# aux_power_systems.net
KiCad netlist of a schematic drawn in EAGLE
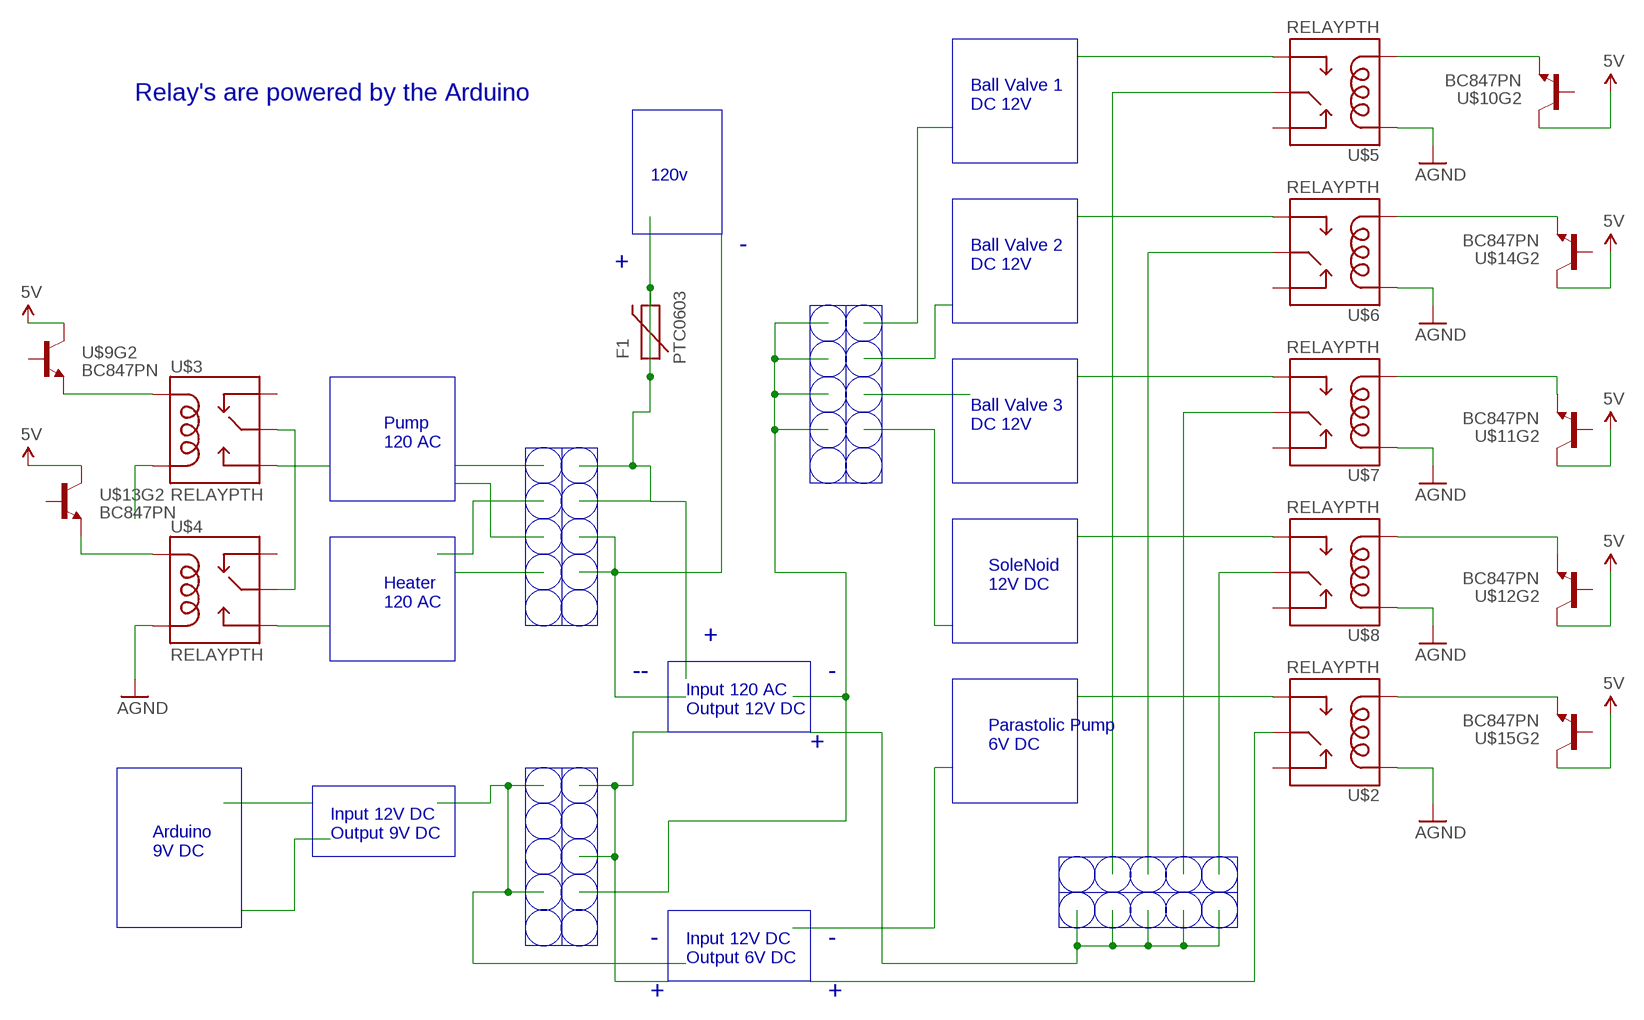
[diagram p0: schematic, sheet 1]

(export (version "E")
  (design (tool "Eeschema 10.0.6"))
  (components
    (comp (ref "F1")
      (value "PTC0603")
      (footprint "eagle-import:0603")
      (libsource (lib "eagle-import") (part "PTC0603"))
    )
    (comp (ref "U$2")
      (value "RELAYPTH")
      (footprint "eagle-import:RELAY-G5Q")
      (libsource (lib "eagle-import") (part "RELAYPTH"))
    )
    (comp (ref "U$3")
      (value "RELAYPTH")
      (footprint "eagle-import:RELAY-G5Q")
      (libsource (lib "eagle-import") (part "RELAYPTH"))
    )
    (comp (ref "U$4")
      (value "RELAYPTH")
      (footprint "eagle-import:RELAY-G5Q")
      (libsource (lib "eagle-import") (part "RELAYPTH"))
    )
    (comp (ref "U$5")
      (value "RELAYPTH")
      (footprint "eagle-import:RELAY-G5Q")
      (libsource (lib "eagle-import") (part "RELAYPTH"))
    )
    (comp (ref "U$6")
      (value "RELAYPTH")
      (footprint "eagle-import:RELAY-G5Q")
      (libsource (lib "eagle-import") (part "RELAYPTH"))
    )
    (comp (ref "U$7")
      (value "RELAYPTH")
      (footprint "eagle-import:RELAY-G5Q")
      (libsource (lib "eagle-import") (part "RELAYPTH"))
    )
    (comp (ref "U$8")
      (value "RELAYPTH")
      (footprint "eagle-import:RELAY-G5Q")
      (libsource (lib "eagle-import") (part "RELAYPTH"))
    )
    (comp (ref "U$9")
      (value "BC847PN")
      (footprint "eagle-import:SOT363")
      (libsource (lib "eagle-import") (part "BC847PN"))
    )
    (comp (ref "U$10")
      (value "BC847PN")
      (footprint "eagle-import:SOT363")
      (libsource (lib "eagle-import") (part "BC847PN"))
    )
    (comp (ref "U$11")
      (value "BC847PN")
      (footprint "eagle-import:SOT363")
      (libsource (lib "eagle-import") (part "BC847PN"))
    )
    (comp (ref "U$12")
      (value "BC847PN")
      (footprint "eagle-import:SOT363")
      (libsource (lib "eagle-import") (part "BC847PN"))
    )
    (comp (ref "U$13")
      (value "BC847PN")
      (footprint "eagle-import:SOT363")
      (libsource (lib "eagle-import") (part "BC847PN"))
    )
    (comp (ref "U$14")
      (value "BC847PN")
      (footprint "eagle-import:SOT363")
      (libsource (lib "eagle-import") (part "BC847PN"))
    )
    (comp (ref "U$15")
      (value "BC847PN")
      (footprint "eagle-import:SOT363")
      (libsource (lib "eagle-import") (part "BC847PN"))
    )
  )
  (nets
    (net (code "2") (name "/B$2") (class "Default")
      (node (ref "U$2") (pin "3") (pinfunction "NO_3") (pintype "bidirectional"))
      (node (ref "U$3") (pin "3") (pinfunction "NO_3") (pintype "bidirectional"))
      (node (ref "U$4") (pin "3") (pinfunction "NO_3") (pintype "bidirectional"))
      (node (ref "U$5") (pin "3") (pinfunction "NO_3") (pintype "bidirectional"))
      (node (ref "U$6") (pin "3") (pinfunction "NO_3") (pintype "bidirectional"))
      (node (ref "U$7") (pin "3") (pinfunction "NO_3") (pintype "bidirectional"))
      (node (ref "U$8") (pin "3") (pinfunction "NO_3") (pintype "bidirectional"))
    )
    (net (code "3") (name "/B$3") (class "Default")
      (node (ref "U$2") (pin "2") (pinfunction "MAIN_2") (pintype "bidirectional"))
      (node (ref "U$7") (pin "2") (pinfunction "MAIN_2") (pintype "bidirectional"))
    )
    (net (code "7") (name "5V") (class "Default")
      (node (ref "U$10") (pin "3") (pinfunction "C_3") (pintype "passive"))
      (node (ref "U$11") (pin "3") (pinfunction "C_3") (pintype "passive"))
      (node (ref "U$12") (pin "3") (pinfunction "C_3") (pintype "passive"))
      (node (ref "U$13") (pin "3") (pinfunction "C_3") (pintype "passive"))
      (node (ref "U$14") (pin "3") (pinfunction "C_3") (pintype "passive"))
      (node (ref "U$15") (pin "3") (pinfunction "C_3") (pintype "passive"))
      (node (ref "U$9") (pin "3") (pinfunction "C_3") (pintype "passive"))
    )
    (net (code "8") (name "AGND") (class "Default")
      (node (ref "U$2") (pin "5") (pinfunction "COIL1_5") (pintype "bidirectional"))
      (node (ref "U$4") (pin "1") (pinfunction "COIL2_1") (pintype "bidirectional"))
      (node (ref "U$5") (pin "5") (pinfunction "COIL1_5") (pintype "bidirectional"))
      (node (ref "U$6") (pin "5") (pinfunction "COIL1_5") (pintype "bidirectional"))
      (node (ref "U$7") (pin "5") (pinfunction "COIL1_5") (pintype "bidirectional"))
      (node (ref "U$8") (pin "5") (pinfunction "COIL1_5") (pintype "bidirectional"))
    )
    (net (code "9") (name "Net-(F1-Pad1)") (class "Default")
      (node (ref "F1") (pin "1") (pinfunction "1_1") (pintype "bidirectional"))
      (node (ref "F1") (pin "2") (pinfunction "2_2") (pintype "bidirectional"))
    )
    (net (code "10") (name "Net-(U$3-COIL1)") (class "Default")
      (node (ref "U$3") (pin "5") (pinfunction "COIL1_5") (pintype "bidirectional"))
      (node (ref "U$9") (pin "4") (pinfunction "E_4") (pintype "passive"))
    )
    (net (code "11") (name "Net-(U$3-MAIN)") (class "Default")
      (node (ref "U$3") (pin "2") (pinfunction "MAIN_2") (pintype "bidirectional"))
      (node (ref "U$4") (pin "2") (pinfunction "MAIN_2") (pintype "bidirectional"))
    )
    (net (code "12") (name "Net-(U$10B-E)") (class "Default")
      (node (ref "U$10") (pin "4") (pinfunction "E_4") (pintype "passive"))
      (node (ref "U$5") (pin "1") (pinfunction "COIL2_1") (pintype "bidirectional"))
    )
    (net (code "13") (name "Net-(U$11B-E)") (class "Default")
      (node (ref "U$11") (pin "4") (pinfunction "E_4") (pintype "passive"))
      (node (ref "U$7") (pin "1") (pinfunction "COIL2_1") (pintype "bidirectional"))
    )
    (net (code "14") (name "Net-(U$12B-E)") (class "Default")
      (node (ref "U$12") (pin "4") (pinfunction "E_4") (pintype "passive"))
      (node (ref "U$8") (pin "1") (pinfunction "COIL2_1") (pintype "bidirectional"))
    )
    (net (code "15") (name "Net-(U$13B-E)") (class "Default")
      (node (ref "U$13") (pin "4") (pinfunction "E_4") (pintype "passive"))
      (node (ref "U$4") (pin "5") (pinfunction "COIL1_5") (pintype "bidirectional"))
    )
    (net (code "16") (name "Net-(U$14B-E)") (class "Default")
      (node (ref "U$14") (pin "4") (pinfunction "E_4") (pintype "passive"))
      (node (ref "U$6") (pin "1") (pinfunction "COIL2_1") (pintype "bidirectional"))
    )
    (net (code "17") (name "Net-(U$15B-E)") (class "Default")
      (node (ref "U$15") (pin "4") (pinfunction "E_4") (pintype "passive"))
      (node (ref "U$2") (pin "1") (pinfunction "COIL2_1") (pintype "bidirectional"))
    )
    (net (code "18") (name "unconnected-(U$2-NC-Pad4)") (class "Default")
      (node (ref "U$2") (pin "4") (pinfunction "NC_4") (pintype "bidirectional"))
    )
    (net (code "19") (name "unconnected-(U$3-COIL2-Pad1)") (class "Default")
      (node (ref "U$3") (pin "1") (pinfunction "COIL2_1") (pintype "bidirectional"))
    )
    (net (code "20") (name "unconnected-(U$3-NC-Pad4)") (class "Default")
      (node (ref "U$3") (pin "4") (pinfunction "NC_4") (pintype "bidirectional"))
    )
    (net (code "21") (name "unconnected-(U$4-NC-Pad4)") (class "Default")
      (node (ref "U$4") (pin "4") (pinfunction "NC_4") (pintype "bidirectional"))
    )
    (net (code "22") (name "unconnected-(U$5-MAIN-Pad2)") (class "Default")
      (node (ref "U$5") (pin "2") (pinfunction "MAIN_2") (pintype "bidirectional"))
    )
    (net (code "23") (name "unconnected-(U$5-NC-Pad4)") (class "Default")
      (node (ref "U$5") (pin "4") (pinfunction "NC_4") (pintype "bidirectional"))
    )
    (net (code "24") (name "unconnected-(U$6-MAIN-Pad2)") (class "Default")
      (node (ref "U$6") (pin "2") (pinfunction "MAIN_2") (pintype "bidirectional"))
    )
    (net (code "25") (name "unconnected-(U$6-NC-Pad4)") (class "Default")
      (node (ref "U$6") (pin "4") (pinfunction "NC_4") (pintype "bidirectional"))
    )
    (net (code "26") (name "unconnected-(U$7-NC-Pad4)") (class "Default")
      (node (ref "U$7") (pin "4") (pinfunction "NC_4") (pintype "bidirectional"))
    )
    (net (code "27") (name "unconnected-(U$8-MAIN-Pad2)") (class "Default")
      (node (ref "U$8") (pin "2") (pinfunction "MAIN_2") (pintype "bidirectional"))
    )
    (net (code "28") (name "unconnected-(U$8-NC-Pad4)") (class "Default")
      (node (ref "U$8") (pin "4") (pinfunction "NC_4") (pintype "bidirectional"))
    )
    (net (code "29") (name "unconnected-(U$9B-B-Pad5)") (class "Default")
      (node (ref "U$9") (pin "5") (pinfunction "B_5") (pintype "passive"))
    )
    (net (code "30") (name "unconnected-(U$10B-B-Pad5)") (class "Default")
      (node (ref "U$10") (pin "5") (pinfunction "B_5") (pintype "passive"))
    )
    (net (code "31") (name "unconnected-(U$11B-B-Pad5)") (class "Default")
      (node (ref "U$11") (pin "5") (pinfunction "B_5") (pintype "passive"))
    )
    (net (code "32") (name "unconnected-(U$12B-B-Pad5)") (class "Default")
      (node (ref "U$12") (pin "5") (pinfunction "B_5") (pintype "passive"))
    )
    (net (code "33") (name "unconnected-(U$13B-B-Pad5)") (class "Default")
      (node (ref "U$13") (pin "5") (pinfunction "B_5") (pintype "passive"))
    )
    (net (code "34") (name "unconnected-(U$14B-B-Pad5)") (class "Default")
      (node (ref "U$14") (pin "5") (pinfunction "B_5") (pintype "passive"))
    )
    (net (code "35") (name "unconnected-(U$15B-B-Pad5)") (class "Default")
      (node (ref "U$15") (pin "5") (pinfunction "B_5") (pintype "passive"))
    )
  )
)
